# schematic.net
KiCad netlist of a schematic drawn in EAGLE
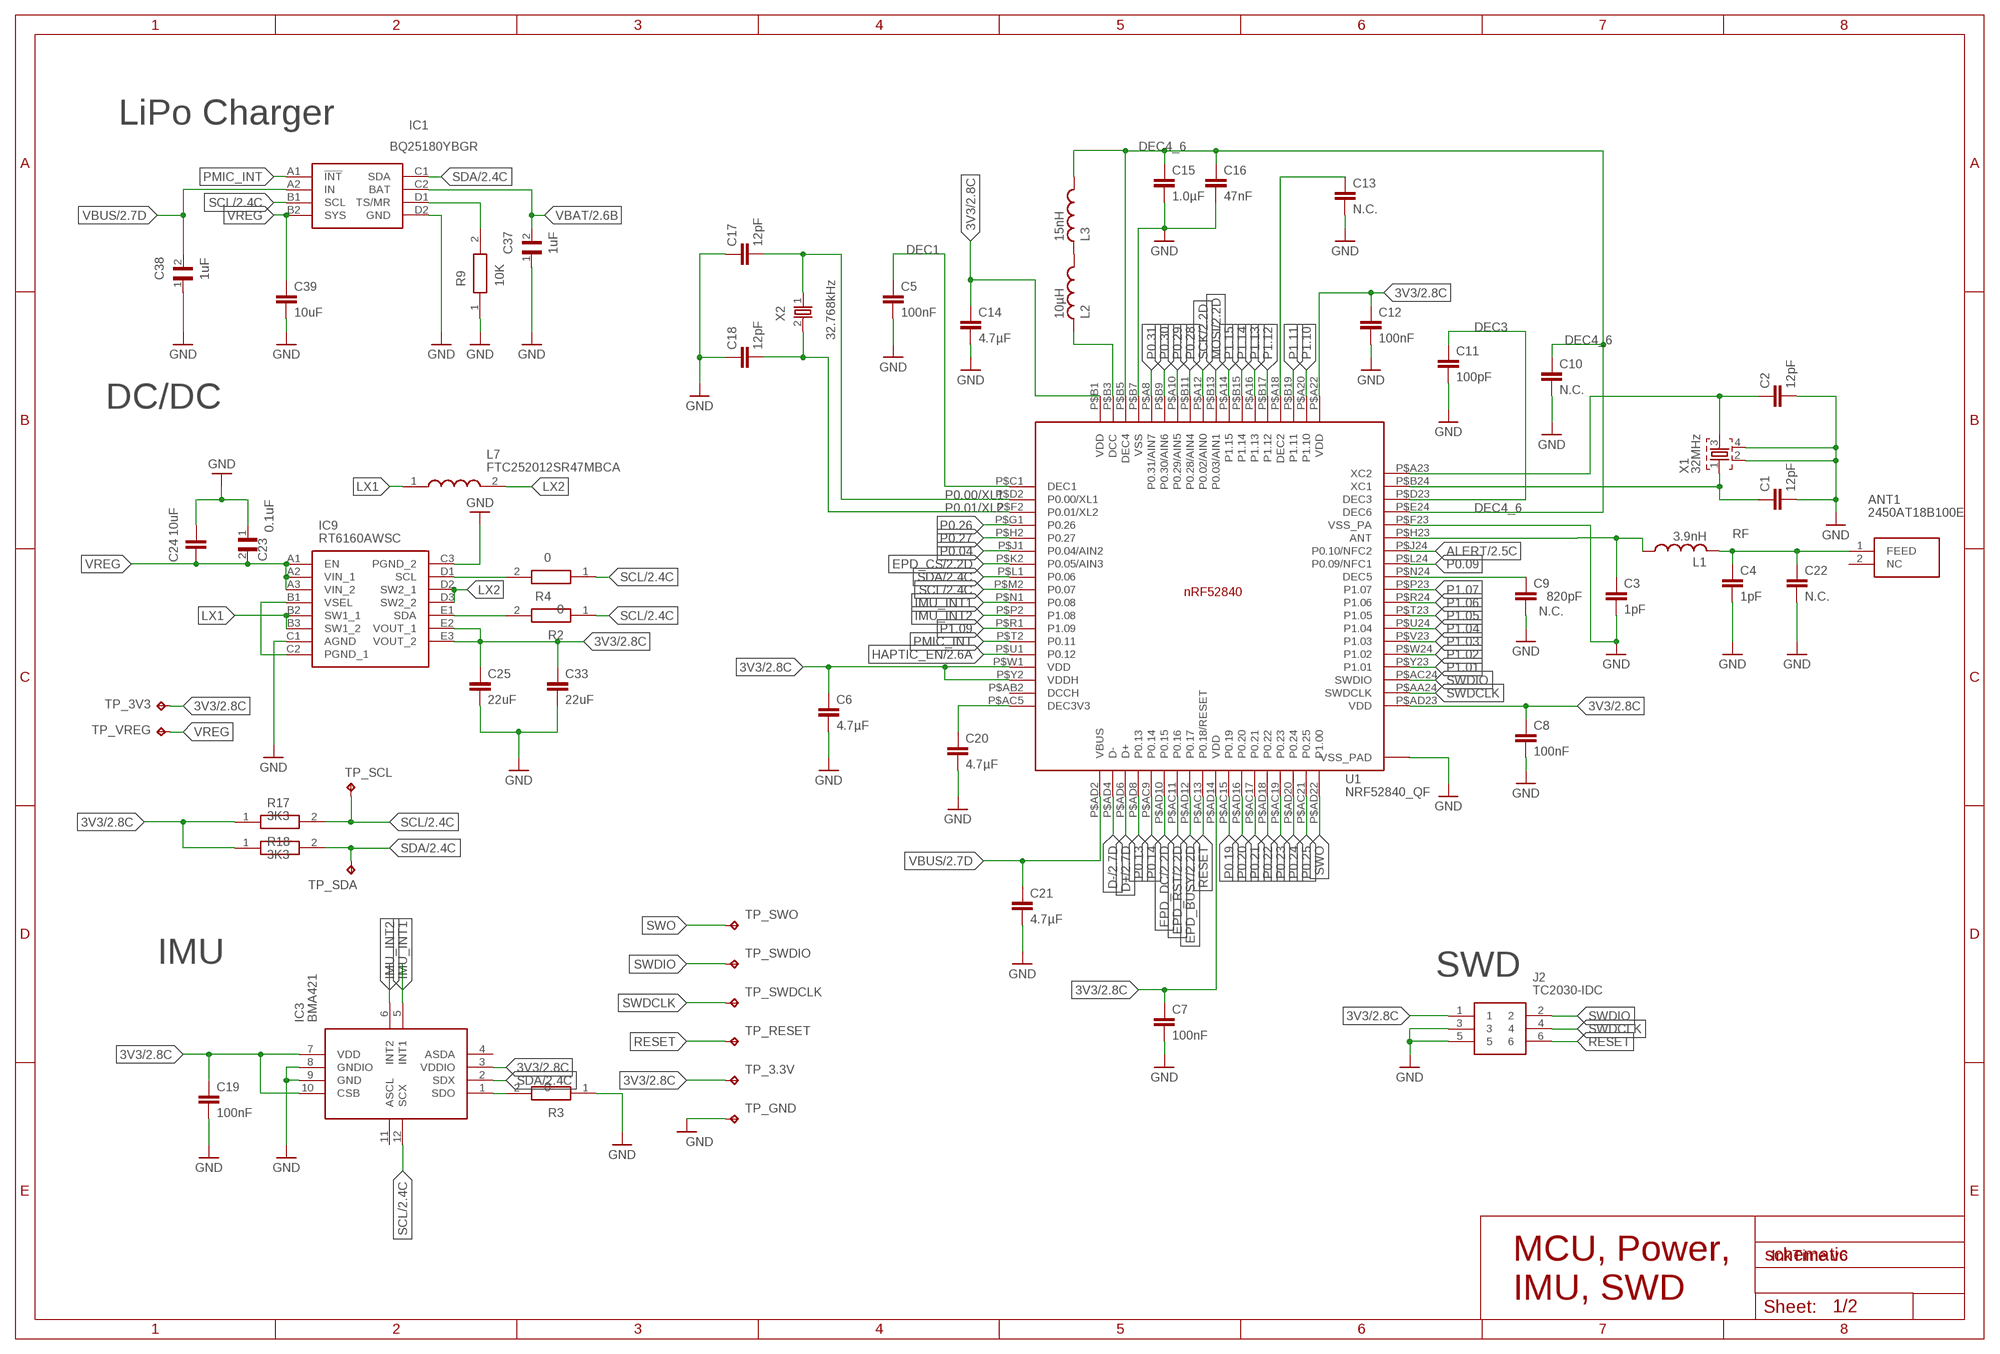
[diagram p0: schematic, sheet 1]
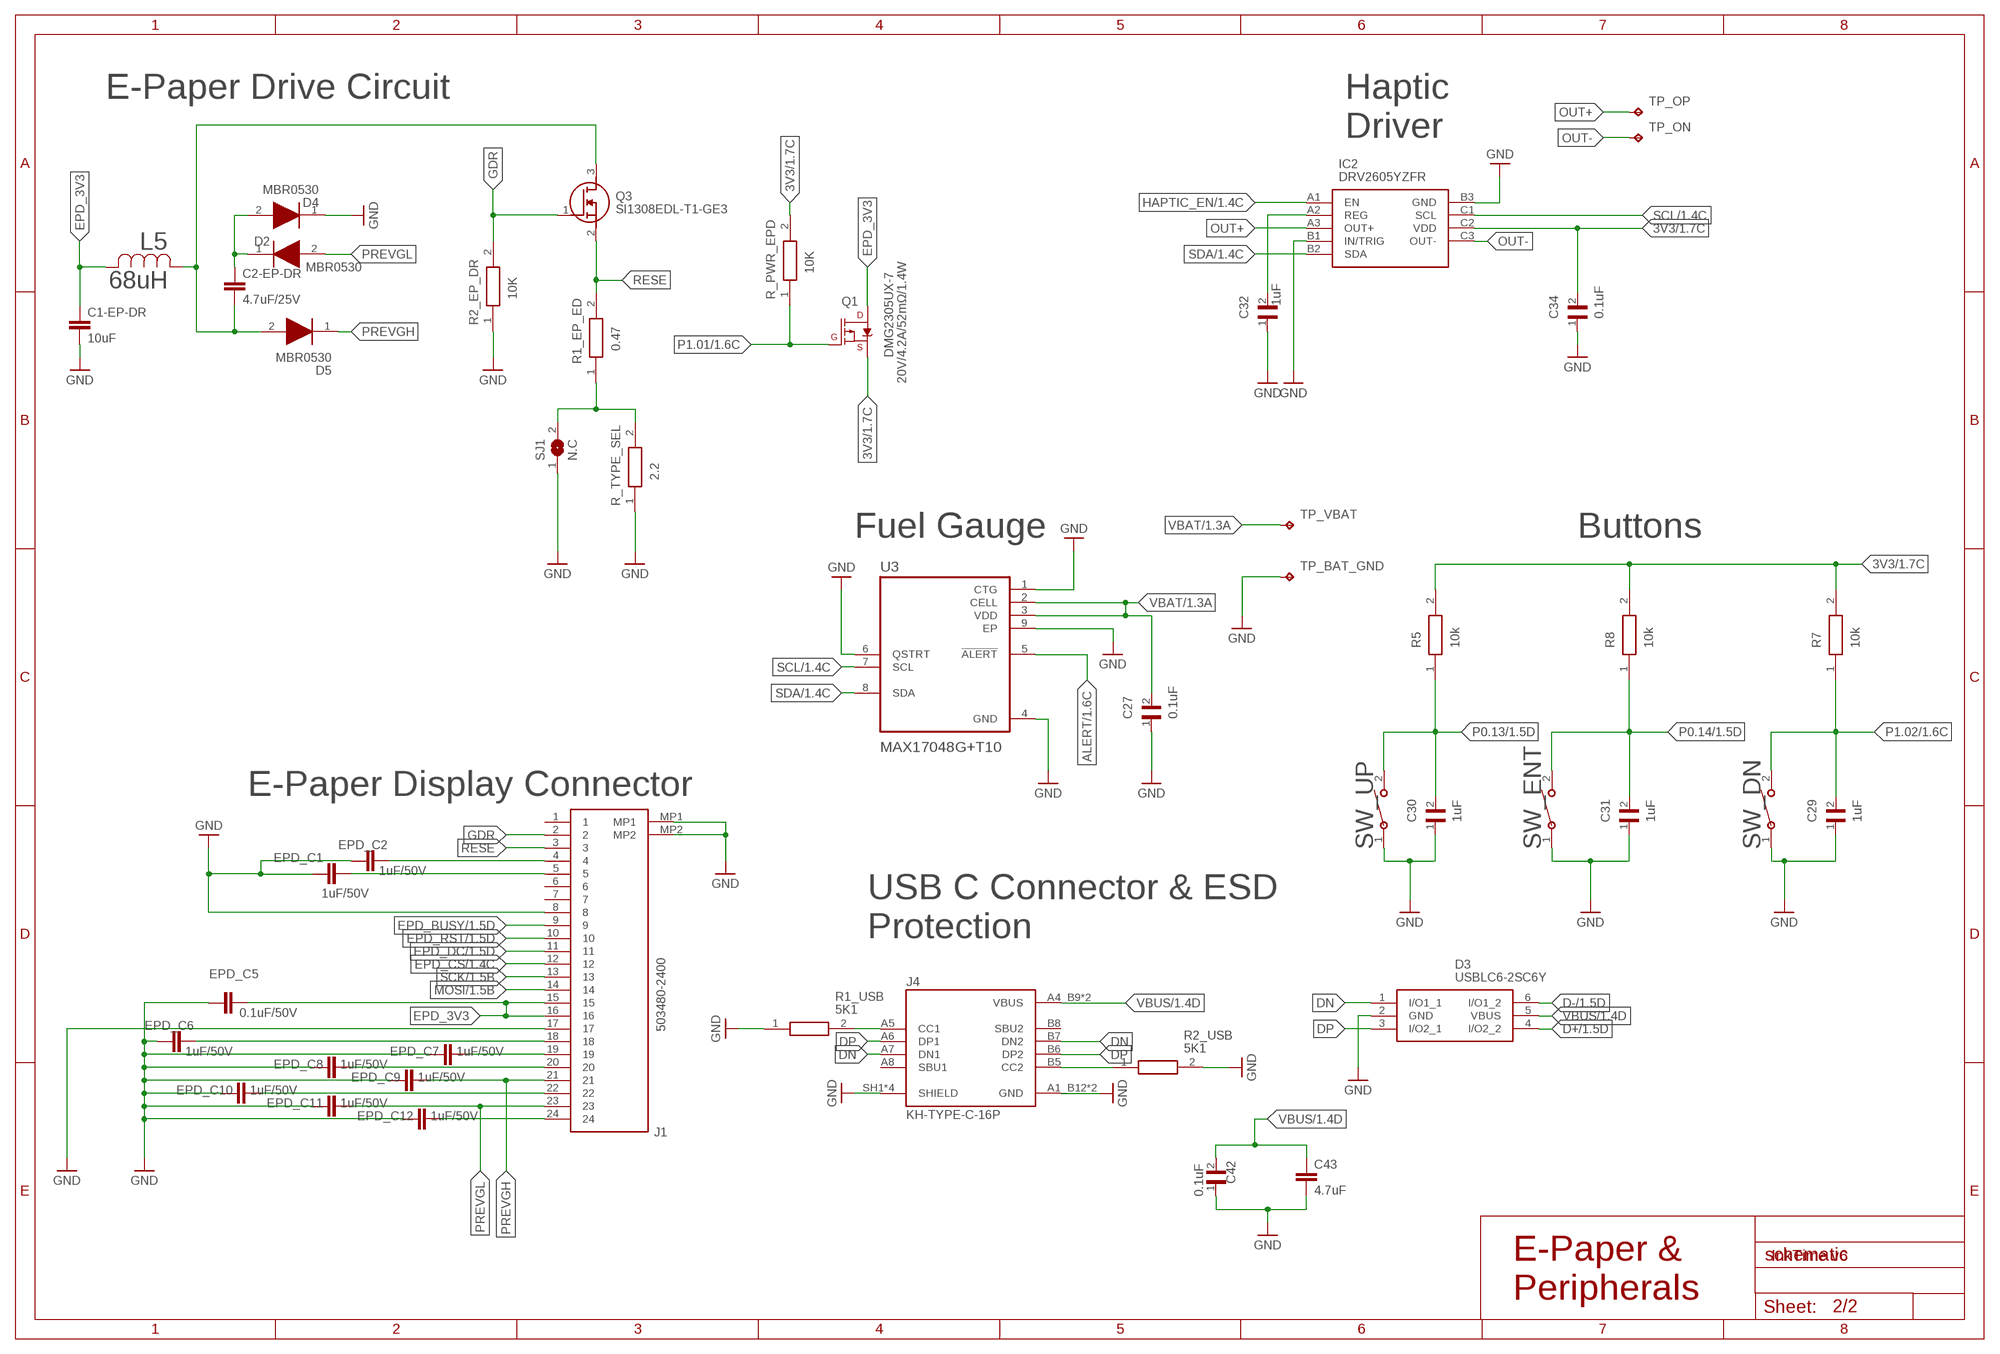
[diagram p1: schematic, sheet 2]

(export (version "E")
  (design (tool "Eeschema 10.0.6"))
  (components
    (comp (ref "C1-EP-DR")
      (value "10uF")
      (footprint "eagle-import:NORDIC_NRF_3_RESC0402_L")
      (libsource (lib "eagle-import") (part "NORDIC_NRF_3_CAPACITOR_0402_L"))
    )
    (comp (ref "C2-EP-DR")
      (value "4.7uF/25V")
      (footprint "eagle-import:NORDIC_NRF_3_RESC0402_L")
      (libsource (lib "eagle-import") (part "NORDIC_NRF_3_CAPACITOR_0402_L"))
    )
    (comp (ref "C27")
      (value "0.1uF")
      (footprint "eagle-import:GRM011R60J152KE01L_2_CAPC0201X13N")
      (fields (field (name "MF") "Murata") (field (name "MP") "GRM011R60J152KE01L"))
      (libsource (lib "eagle-import") (part "GRM011R60J152KE01L_2_GRM011R60J152KE01L"))
    )
    (comp (ref "C29")
      (value "1uF")
      (footprint "eagle-import:GRM011R60J152KE01L_2_CAPC0201X13N")
      (fields (field (name "MF") "Murata") (field (name "MP") "GRM011R60J152KE01L"))
      (libsource (lib "eagle-import") (part "GRM011R60J152KE01L_2_GRM011R60J152KE01L"))
    )
    (comp (ref "C30")
      (value "1uF")
      (footprint "eagle-import:GRM011R60J152KE01L_2_CAPC0201X13N")
      (fields (field (name "MF") "Murata") (field (name "MP") "GRM011R60J152KE01L"))
      (libsource (lib "eagle-import") (part "GRM011R60J152KE01L_2_GRM011R60J152KE01L"))
    )
    (comp (ref "C31")
      (value "1uF")
      (footprint "eagle-import:GRM011R60J152KE01L_2_CAPC0201X13N")
      (fields (field (name "MF") "Murata") (field (name "MP") "GRM011R60J152KE01L"))
      (libsource (lib "eagle-import") (part "GRM011R60J152KE01L_2_GRM011R60J152KE01L"))
    )
    (comp (ref "C32")
      (value "1uF")
      (footprint "eagle-import:GRM011R60J152KE01L_2_CAPC0201X13N")
      (fields (field (name "MF") "Murata") (field (name "MP") "GRM011R60J152KE01L"))
      (libsource (lib "eagle-import") (part "GRM011R60J152KE01L_2_GRM011R60J152KE01L"))
    )
    (comp (ref "C34")
      (value "0.1uF")
      (footprint "eagle-import:GRM011R60J152KE01L_2_CAPC0201X13N")
      (fields (field (name "MF") "Murata") (field (name "MP") "GRM011R60J152KE01L"))
      (libsource (lib "eagle-import") (part "GRM011R60J152KE01L_2_GRM011R60J152KE01L"))
    )
    (comp (ref "C42")
      (value "0.1uF")
      (footprint "eagle-import:GRM011R60J152KE01L_2_CAPC0201X13N")
      (fields (field (name "MF") "Murata") (field (name "MP") "GRM011R60J152KE01L"))
      (libsource (lib "eagle-import") (part "GRM011R60J152KE01L_2_GRM011R60J152KE01L"))
    )
    (comp (ref "C43")
      (value "4.7uF")
      (footprint "eagle-import:NORDIC_NRF_3_RESC0402_L")
      (libsource (lib "eagle-import") (part "NORDIC_NRF_3_CAPACITOR_0402_L"))
    )
    (comp (ref "D2")
      (value "MBR0530")
      (footprint "eagle-import:ESP32_C6_LIBRARY_5_SOD3716X135N")
      (fields (field (name "MF") "ON Semiconductor"))
      (libsource (lib "eagle-import") (part "ESP32_C6_LIBRARY_5_MBR0530"))
    )
    (comp (ref "D3")
      (value "USBLC6-2SC6Y")
      (footprint "eagle-import:ESP32_C6_LIBRARY_3_SOT95P280X145-6N")
      (fields (field (name "MF") "STMicroelectronics"))
      (libsource (lib "eagle-import") (part "ESP32_C6_LIBRARY_3_USBLC6-2SC6Y"))
    )
    (comp (ref "D4")
      (value "MBR0530")
      (footprint "eagle-import:ESP32_C6_LIBRARY_5_SOD3716X135N")
      (fields (field (name "MF") "ON Semiconductor"))
      (libsource (lib "eagle-import") (part "ESP32_C6_LIBRARY_5_MBR0530"))
    )
    (comp (ref "D5")
      (value "MBR0530")
      (footprint "eagle-import:ESP32_C6_LIBRARY_5_SOD3716X135N")
      (fields (field (name "MF") "ON Semiconductor"))
      (libsource (lib "eagle-import") (part "ESP32_C6_LIBRARY_5_MBR0530"))
    )
    (comp (ref "EPD_C1")
      (value "1uF/50V")
      (footprint "eagle-import:NORDIC_NRF_3_RESC0201_L")
      (libsource (lib "eagle-import") (part "NORDIC_NRF_3_CAPACITOR_0201_L"))
    )
    (comp (ref "EPD_C2")
      (value "1uF/50V")
      (footprint "eagle-import:NORDIC_NRF_3_RESC0201_L")
      (libsource (lib "eagle-import") (part "NORDIC_NRF_3_CAPACITOR_0201_L"))
    )
    (comp (ref "EPD_C5")
      (value "0.1uF/50V")
      (footprint "eagle-import:NORDIC_NRF_3_RESC0201_L")
      (libsource (lib "eagle-import") (part "NORDIC_NRF_3_CAPACITOR_0201_L"))
    )
    (comp (ref "EPD_C6")
      (value "1uF/50V")
      (footprint "eagle-import:NORDIC_NRF_3_RESC0402_L")
      (libsource (lib "eagle-import") (part "NORDIC_NRF_3_CAPACITOR_0402_L"))
    )
    (comp (ref "EPD_C7")
      (value "1uF/50V")
      (footprint "eagle-import:NORDIC_NRF_3_RESC0402_L")
      (libsource (lib "eagle-import") (part "NORDIC_NRF_3_CAPACITOR_0402_L"))
    )
    (comp (ref "EPD_C8")
      (value "1uF/50V")
      (footprint "eagle-import:NORDIC_NRF_3_RESC0402_L")
      (libsource (lib "eagle-import") (part "NORDIC_NRF_3_CAPACITOR_0402_L"))
    )
    (comp (ref "EPD_C9")
      (value "1uF/50V")
      (footprint "eagle-import:NORDIC_NRF_3_RESC0402_L")
      (libsource (lib "eagle-import") (part "NORDIC_NRF_3_CAPACITOR_0402_L"))
    )
    (comp (ref "EPD_C10")
      (value "1uF/50V")
      (footprint "eagle-import:NORDIC_NRF_3_RESC0402_L")
      (libsource (lib "eagle-import") (part "NORDIC_NRF_3_CAPACITOR_0402_L"))
    )
    (comp (ref "EPD_C11")
      (value "1uF/50V")
      (footprint "eagle-import:NORDIC_NRF_3_RESC0402_L")
      (libsource (lib "eagle-import") (part "NORDIC_NRF_3_CAPACITOR_0402_L"))
    )
    (comp (ref "EPD_C12")
      (value "1uF/50V")
      (footprint "eagle-import:NORDIC_NRF_3_RESC0402_L")
      (libsource (lib "eagle-import") (part "NORDIC_NRF_3_CAPACITOR_0402_L"))
    )
    (comp (ref "IC2")
      (value "DRV2605YZFR")
      (footprint "eagle-import:DRV2605YZFR_BGA9C50P3X3_144X144X62")
      (libsource (lib "eagle-import") (part "DRV2605YZFR_DRV2605YZFR"))
    )
    (comp (ref "J1")
      (value "503480-2400")
      (footprint "eagle-import:503480-2400_5034802400")
      (fields (field (name "MOUSER_PART_NUMBER") "538-503480-2400"))
      (libsource (lib "eagle-import") (part "503480-2400_503480-2400"))
    )
    (comp (ref "J4")
      (value "KH-TYPE-C-16P")
      (footprint "eagle-import:KH-TYPE-C-16P_KINGHELM_KH-TYPE-C-16P")
      (fields (field (name "MF") "kinghelm"))
      (libsource (lib "eagle-import") (part "KH-TYPE-C-16P_KH-TYPE-C-16P"))
    )
    (comp (ref "L5")
      (value "68uH")
      (footprint "eagle-import:ESP32_C6_LIBRARY_2_IND_4828-WE-TPC_WRE")
      (fields
        (field (name "MANUFACTURER_PART_NUMBER") "744043680")
        (field (name "COPYRIGHT") "Copyright (C) 2024 Ultra Librarian. All rights reserved.")
      )
      (libsource (lib "eagle-import") (part "ESP32_C6_LIBRARY_2_744043680IND_4828-WE-TPC_WRE"))
    )
    (comp (ref "Q1")
      (value "20V/4.2A/52mΩ/1.4W")
      (footprint "eagle-import:ESP32_C6_LIBRARY_4_ESP32_C6_LIBRARY_4_ESP32_C6_LIBRARY_4_ESP32_C6_LIBRARY_4_ESP32_WROVER_SPARKFUN-DISCRETESEMI_SOT23-3")
      (libsource (lib "eagle-import") (part "ESP32_C6_LIBRARY_4_ESP32_WROVER_SPARKFUN-DISCRETESEMI_MOSFET_PCH-DMG2305UX-7"))
    )
    (comp (ref "Q3")
      (value "SI1308EDL-T1-GE3")
      (footprint "eagle-import:ESP32_C6_LIBRARY_6_SOT65P210X110-3N")
      (fields (field (name "MF") "Vishay Siliconix"))
      (libsource (lib "eagle-import") (part "ESP32_C6_LIBRARY_6_SI1308EDL-T1-GE3"))
    )
    (comp (ref "R1_EP_ED")
      (value "0.47")
      (footprint "eagle-import:CPF0201D7K68C1_0201")
      (libsource (lib "eagle-import") (part "CPF0201D7K68C1_CPF0201D7K68C1"))
    )
    (comp (ref "R1_USB")
      (value "5K1")
      (footprint "eagle-import:CPF0201D7K68C1_0201")
      (libsource (lib "eagle-import") (part "CPF0201D7K68C1_CPF0201D7K68C1"))
    )
    (comp (ref "R2_EP_DR")
      (value "10K")
      (footprint "eagle-import:CPF0201D7K68C1_0201")
      (libsource (lib "eagle-import") (part "CPF0201D7K68C1_CPF0201D7K68C1"))
    )
    (comp (ref "R2_USB")
      (value "5K1")
      (footprint "eagle-import:CPF0201D7K68C1_0201")
      (libsource (lib "eagle-import") (part "CPF0201D7K68C1_CPF0201D7K68C1"))
    )
    (comp (ref "R5")
      (value "10k")
      (footprint "eagle-import:ERA-1AEB3401C_0201")
      (libsource (lib "eagle-import") (part "ERA-1AEB3401C_CPF0201D7K68C1"))
    )
    (comp (ref "R7")
      (value "10k")
      (footprint "eagle-import:ERA-1AEB3401C_0201")
      (libsource (lib "eagle-import") (part "ERA-1AEB3401C_CPF0201D7K68C1"))
    )
    (comp (ref "R8")
      (value "10k")
      (footprint "eagle-import:ERA-1AEB3401C_0201")
      (libsource (lib "eagle-import") (part "ERA-1AEB3401C_CPF0201D7K68C1"))
    )
    (comp (ref "R_PWR_EPD")
      (value "10K")
      (footprint "eagle-import:CPF0201D7K68C1_0201")
      (libsource (lib "eagle-import") (part "CPF0201D7K68C1_CPF0201D7K68C1"))
    )
    (comp (ref "R_TYPE_SEL")
      (value "2.2")
      (footprint "eagle-import:CPF0201D7K68C1_0201")
      (libsource (lib "eagle-import") (part "CPF0201D7K68C1_CPF0201D7K68C1"))
    )
    (comp (ref "SJ1")
      (value "N.C")
      (footprint "eagle-import:ESP32_C6_LIBRARY_7_JUMPER_SJ")
      (libsource (lib "eagle-import") (part "ESP32_C6_LIBRARY_7_JUMPER_SJ"))
    )
    (comp (ref "SW_DN")
      (value "2025-10-22_07-23-44_LIBRARY_EVP-AKE31ASW_EVP-AKE31A_PAN")
      (footprint "eagle-import:2025-10-22_07-23-44_LIBRARY_SW_EVP-AKE31A_PAN")
      (fields
        (field (name "MANUFACTURER_PART_NUMBER") "EVP-AKE31A")
        (field (name "COPYRIGHT") "Copyright (C) 2025 Ultra Librarian. All rights reserved.")
      )
      (libsource (lib "eagle-import") (part "2025-10-22_07-23-44_LIBRARY_EVP-AKE31ASW_EVP-AKE31A_PAN"))
    )
    (comp (ref "SW_ENT")
      (value "2025-10-22_07-23-44_LIBRARY_EVP-AKE31ASW_EVP-AKE31A_PAN")
      (footprint "eagle-import:2025-10-22_07-23-44_LIBRARY_SW_EVP-AKE31A_PAN")
      (fields
        (field (name "MANUFACTURER_PART_NUMBER") "EVP-AKE31A")
        (field (name "COPYRIGHT") "Copyright (C) 2025 Ultra Librarian. All rights reserved.")
      )
      (libsource (lib "eagle-import") (part "2025-10-22_07-23-44_LIBRARY_EVP-AKE31ASW_EVP-AKE31A_PAN"))
    )
    (comp (ref "SW_UP")
      (value "2025-10-22_07-23-44_LIBRARY_EVP-AKE31ASW_EVP-AKE31A_PAN")
      (footprint "eagle-import:2025-10-22_07-23-44_LIBRARY_SW_EVP-AKE31A_PAN")
      (fields
        (field (name "MANUFACTURER_PART_NUMBER") "EVP-AKE31A")
        (field (name "COPYRIGHT") "Copyright (C) 2025 Ultra Librarian. All rights reserved.")
      )
      (libsource (lib "eagle-import") (part "2025-10-22_07-23-44_LIBRARY_EVP-AKE31ASW_EVP-AKE31A_PAN"))
    )
    (comp (ref "TP_BAT_GND")
      (value "HECTOR_WATCH_1_TPTP20R")
      (footprint "eagle-import:HECTOR_WATCH_1_TP20R")
      (libsource (lib "eagle-import") (part "HECTOR_WATCH_1_TPTP20R"))
    )
    (comp (ref "TP_ON")
      (value "HECTOR_WATCH_1_TPTP20R")
      (footprint "eagle-import:HECTOR_WATCH_1_TP20R")
      (libsource (lib "eagle-import") (part "HECTOR_WATCH_1_TPTP20R"))
    )
    (comp (ref "TP_OP")
      (value "HECTOR_WATCH_1_TPTP20R")
      (footprint "eagle-import:HECTOR_WATCH_1_TP20R")
      (libsource (lib "eagle-import") (part "HECTOR_WATCH_1_TPTP20R"))
    )
    (comp (ref "TP_VBAT")
      (value "HECTOR_WATCH_1_TPTP20R")
      (footprint "eagle-import:HECTOR_WATCH_1_TP20R")
      (libsource (lib "eagle-import") (part "HECTOR_WATCH_1_TPTP20R"))
    )
    (comp (ref "U3")
      (value "MAX17048G+T10")
      (footprint "eagle-import:ESP32_C6_LIBRARY_SON50P200X200X80-9N")
      (fields (field (name "MF") "Analog Devices"))
      (libsource (lib "eagle-import") (part "ESP32_C6_LIBRARY_MAX17048G+T10"))
    )
    (comp (ref "ANT1")
      (value "2450AT18B100E")
      (footprint "eagle-import:2450AT18B100E_ANTC3216X140N")
      (fields (field (name "MOUSER_PART_NUMBER") "609-2450AT18B100E"))
      (libsource (lib "eagle-import") (part "2450AT18B100E_2450AT18B100E"))
    )
    (comp (ref "C1")
      (value "12pF")
      (footprint "eagle-import:NORDIC_NRF_3_RESC0201_L")
      (libsource (lib "eagle-import") (part "NORDIC_NRF_3_CAPACITOR_0201_L"))
    )
    (comp (ref "C2")
      (value "12pF")
      (footprint "eagle-import:NORDIC_NRF_3_RESC0201_L")
      (libsource (lib "eagle-import") (part "NORDIC_NRF_3_CAPACITOR_0201_L"))
    )
    (comp (ref "C3")
      (value "1pF")
      (footprint "eagle-import:NORDIC_NRF_3_RESC0201_L")
      (libsource (lib "eagle-import") (part "NORDIC_NRF_3_CAPACITOR_0201_L"))
    )
    (comp (ref "C4")
      (value "1pF")
      (footprint "eagle-import:NORDIC_NRF_3_RESC0201_L")
      (libsource (lib "eagle-import") (part "NORDIC_NRF_3_CAPACITOR_0201_L"))
    )
    (comp (ref "C5")
      (value "100nF")
      (footprint "eagle-import:NORDIC_NRF_3_RESC0201_L")
      (libsource (lib "eagle-import") (part "NORDIC_NRF_3_CAPACITOR_0201_L"))
    )
    (comp (ref "C6")
      (value "4.7µF")
      (footprint "eagle-import:NORDIC_NRF_3_RESC0402_L")
      (libsource (lib "eagle-import") (part "NORDIC_NRF_3_CAPACITOR_0402_L"))
    )
    (comp (ref "C7")
      (value "100nF")
      (footprint "eagle-import:NORDIC_NRF_3_RESC0201_L")
      (libsource (lib "eagle-import") (part "NORDIC_NRF_3_CAPACITOR_0201_L"))
    )
    (comp (ref "C8")
      (value "100nF")
      (footprint "eagle-import:NORDIC_NRF_3_RESC0201_L")
      (libsource (lib "eagle-import") (part "NORDIC_NRF_3_CAPACITOR_0201_L"))
    )
    (comp (ref "C9")
      (value "820pF")
      (footprint "eagle-import:NORDIC_NRF_3_RESC0201_L")
      (libsource (lib "eagle-import") (part "NORDIC_NRF_3_CAPACITOR_0201_L"))
    )
    (comp (ref "C10")
      (value "N.C.")
      (footprint "eagle-import:NORDIC_NRF_3_RESC0201_L")
      (libsource (lib "eagle-import") (part "NORDIC_NRF_3_CAPACITOR_0201_L"))
    )
    (comp (ref "C11")
      (value "100pF")
      (footprint "eagle-import:NORDIC_NRF_3_RESC0201_L")
      (libsource (lib "eagle-import") (part "NORDIC_NRF_3_CAPACITOR_0201_L"))
    )
    (comp (ref "C12")
      (value "100nF")
      (footprint "eagle-import:NORDIC_NRF_3_RESC0201_L")
      (libsource (lib "eagle-import") (part "NORDIC_NRF_3_CAPACITOR_0201_L"))
    )
    (comp (ref "C13")
      (value "N.C.")
      (footprint "eagle-import:NORDIC_NRF_3_RESC0201_L")
      (libsource (lib "eagle-import") (part "NORDIC_NRF_3_CAPACITOR_0201_L"))
    )
    (comp (ref "C14")
      (value "4.7µF")
      (footprint "eagle-import:NORDIC_NRF_3_RESC0402_L")
      (libsource (lib "eagle-import") (part "NORDIC_NRF_3_CAPACITOR_0402_L"))
    )
    (comp (ref "C15")
      (value "1.0µF")
      (footprint "eagle-import:NORDIC_NRF_3_RESC0402_L")
      (libsource (lib "eagle-import") (part "NORDIC_NRF_3_CAPACITOR_0402_L"))
    )
    (comp (ref "C16")
      (value "47nF")
      (footprint "eagle-import:NORDIC_NRF_3_RESC0201_L")
      (libsource (lib "eagle-import") (part "NORDIC_NRF_3_CAPACITOR_0201_L"))
    )
    (comp (ref "C17")
      (value "12pF")
      (footprint "eagle-import:NORDIC_NRF_3_RESC0201_L")
      (libsource (lib "eagle-import") (part "NORDIC_NRF_3_CAPACITOR_0201_L"))
    )
    (comp (ref "C18")
      (value "12pF")
      (footprint "eagle-import:NORDIC_NRF_3_RESC0201_L")
      (libsource (lib "eagle-import") (part "NORDIC_NRF_3_CAPACITOR_0201_L"))
    )
    (comp (ref "C19")
      (value "100nF")
      (footprint "eagle-import:NORDIC_NRF_3_RESC0201_L")
      (libsource (lib "eagle-import") (part "NORDIC_NRF_3_CAPACITOR_0201_L"))
    )
    (comp (ref "C20")
      (value "4.7µF")
      (footprint "eagle-import:NORDIC_NRF_3_RESC0402_L")
      (libsource (lib "eagle-import") (part "NORDIC_NRF_3_CAPACITOR_0402_L"))
    )
    (comp (ref "C21")
      (value "4.7µF")
      (footprint "eagle-import:NORDIC_NRF_3_RESC0402_L")
      (libsource (lib "eagle-import") (part "NORDIC_NRF_3_CAPACITOR_0402_L"))
    )
    (comp (ref "C22")
      (value "N.C.")
      (footprint "eagle-import:NORDIC_NRF_3_RESC0201_L")
      (libsource (lib "eagle-import") (part "NORDIC_NRF_3_CAPACITOR_0201_L"))
    )
    (comp (ref "C23")
      (value "0.1uF")
      (footprint "eagle-import:GRM011R60J152KE01L_2_CAPC0201X13N")
      (fields (field (name "MF") "Murata") (field (name "MP") "GRM011R60J152KE01L"))
      (libsource (lib "eagle-import") (part "GRM011R60J152KE01L_2_GRM011R60J152KE01L"))
    )
    (comp (ref "C24")
      (value "10uF")
      (footprint "eagle-import:NORDIC_NRF_3_RESC0201_L")
      (libsource (lib "eagle-import") (part "NORDIC_NRF_3_CAPACITOR_0201_L"))
    )
    (comp (ref "C25")
      (value "22uF")
      (footprint "eagle-import:NORDIC_NRF_3_RESC0201_L")
      (libsource (lib "eagle-import") (part "NORDIC_NRF_3_CAPACITOR_0201_L"))
    )
    (comp (ref "C33")
      (value "22uF")
      (footprint "eagle-import:NORDIC_NRF_3_RESC0201_L")
      (libsource (lib "eagle-import") (part "NORDIC_NRF_3_CAPACITOR_0201_L"))
    )
    (comp (ref "C37")
      (value "1uF")
      (footprint "eagle-import:GRM011R60J152KE01L_2_CAPC0201X13N")
      (fields (field (name "MF") "Murata") (field (name "MP") "GRM011R60J152KE01L"))
      (libsource (lib "eagle-import") (part "GRM011R60J152KE01L_2_GRM011R60J152KE01L"))
    )
    (comp (ref "C38")
      (value "1uF")
      (footprint "eagle-import:GRM011R60J152KE01L_2_CAPC0201X13N")
      (fields (field (name "MF") "Murata") (field (name "MP") "GRM011R60J152KE01L"))
      (libsource (lib "eagle-import") (part "GRM011R60J152KE01L_2_GRM011R60J152KE01L"))
    )
    (comp (ref "C39")
      (value "10uF")
      (footprint "eagle-import:PERFECT_0402_0402")
      (libsource (lib "eagle-import") (part "PERFECT_0402_CAP_0402"))
    )
    (comp (ref "IC1")
      (value "BQ25180YBGR_BQ25180YBGR")
      (footprint "eagle-import:BQ25180YBGR_BGA8C40P2X4_100X155X50")
      (fields
        (field (name "ARROW_PART_NUMBER") "BQ25180YBGR")
        (field (name "MANUFACTURER_PART_NUMBER") "BQ25180YBGR")
        (field (name "MOUSER_PART_NUMBER") "595-BQ25180YBGR")
      )
      (libsource (lib "eagle-import") (part "BQ25180YBGR_BQ25180YBGR"))
    )
    (comp (ref "IC3")
      (value "BMA421")
      (footprint "eagle-import:BMA423_BMA423")
      (fields (field (name "ARROW_PART_NUMBER") "BMA423") (field (name "MOUSER_PART_NUMBER") "262-BMA423"))
      (libsource (lib "eagle-import") (part "BMA423_BMA423"))
    )
    (comp (ref "IC9")
      (value "RT6160AWSC")
      (footprint "eagle-import:RT6160AWSC_BGA15C40P3X5_140X230X60")
      (fields (field (name "MOUSER_PART_NUMBER") "835-RT6160AWSC"))
      (libsource (lib "eagle-import") (part "RT6160AWSC_RT6160AWSC"))
    )
    (comp (ref "J2")
      (value "TC2030-IDC")
      (footprint "eagle-import:TC2030-IDC_TC2030IDC")
      (libsource (lib "eagle-import") (part "TC2030-IDC_TC2030-IDC"))
    )
    (comp (ref "L1")
      (value "3.9nH")
      (footprint "eagle-import:NORDIC_NRF_2_RESC0402_L")
      (libsource (lib "eagle-import") (part "NORDIC_NRF_2_INDUCTOR_0402_L"))
    )
    (comp (ref "L2")
      (value "10µH")
      (footprint "eagle-import:NORDIC_NRF_2_RESC0402_L")
      (libsource (lib "eagle-import") (part "NORDIC_NRF_2_INDUCTOR_0402_L"))
    )
    (comp (ref "L3")
      (value "15nH")
      (footprint "eagle-import:NORDIC_NRF_2_RESC0402_L")
      (libsource (lib "eagle-import") (part "NORDIC_NRF_2_INDUCTOR_0402_L"))
    )
    (comp (ref "L7")
      (value "FTC252012SR47MBCA")
      (footprint "eagle-import:MLP2016SR47MT0S1_INDC2016X100N")
      (libsource (lib "eagle-import") (part "MLP2016SR47MT0S1_FTC252012SR47MBCA"))
    )
    (comp (ref "R2")
      (value "0")
      (footprint "eagle-import:CPF0201D7K68C1_0201")
      (libsource (lib "eagle-import") (part "CPF0201D7K68C1_CPF0201D7K68C1"))
    )
    (comp (ref "R3")
      (value "0")
      (footprint "eagle-import:ERA-1AEB3401C_0201")
      (libsource (lib "eagle-import") (part "ERA-1AEB3401C_CPF0201D7K68C1"))
    )
    (comp (ref "R4")
      (value "0")
      (footprint "eagle-import:CPF0201D7K68C1_0201")
      (libsource (lib "eagle-import") (part "CPF0201D7K68C1_CPF0201D7K68C1"))
    )
    (comp (ref "R9")
      (value "10K")
      (footprint "eagle-import:ERA-1AEB3401C_0201")
      (libsource (lib "eagle-import") (part "ERA-1AEB3401C_CPF0201D7K68C1"))
    )
    (comp (ref "R17")
      (value "3K3")
      (footprint "eagle-import:CPF0201D7K68C1_0201")
      (libsource (lib "eagle-import") (part "CPF0201D7K68C1_CPF0201D7K68C1"))
    )
    (comp (ref "R18")
      (value "3K3")
      (footprint "eagle-import:CPF0201D7K68C1_0201")
      (libsource (lib "eagle-import") (part "CPF0201D7K68C1_CPF0201D7K68C1"))
    )
    (comp (ref "TP_3.3V")
      (value "HECTOR_WATCH_1_TPTP20R")
      (footprint "eagle-import:HECTOR_WATCH_1_TP20R")
      (libsource (lib "eagle-import") (part "HECTOR_WATCH_1_TPTP20R"))
    )
    (comp (ref "TP_3V3")
      (value "HECTOR_WATCH_1_TPTP20R")
      (footprint "eagle-import:HECTOR_WATCH_1_TP20R")
      (libsource (lib "eagle-import") (part "HECTOR_WATCH_1_TPTP20R"))
    )
    (comp (ref "TP_GND")
      (value "HECTOR_WATCH_1_TPTP20R")
      (footprint "eagle-import:HECTOR_WATCH_1_TP20R")
      (libsource (lib "eagle-import") (part "HECTOR_WATCH_1_TPTP20R"))
    )
    (comp (ref "TP_RESET")
      (value "HECTOR_WATCH_1_TPTP20R")
      (footprint "eagle-import:HECTOR_WATCH_1_TP20R")
      (libsource (lib "eagle-import") (part "HECTOR_WATCH_1_TPTP20R"))
    )
    (comp (ref "TP_SCL")
      (value "HECTOR_WATCH_1_TPTP20R")
      (footprint "eagle-import:HECTOR_WATCH_1_TP20R")
      (libsource (lib "eagle-import") (part "HECTOR_WATCH_1_TPTP20R"))
    )
    (comp (ref "TP_SDA")
      (value "HECTOR_WATCH_1_TPTP20R")
      (footprint "eagle-import:HECTOR_WATCH_1_TP20R")
      (libsource (lib "eagle-import") (part "HECTOR_WATCH_1_TPTP20R"))
    )
    (comp (ref "TP_SWDCLK")
      (value "HECTOR_WATCH_1_TPTP20R")
      (footprint "eagle-import:HECTOR_WATCH_1_TP20R")
      (libsource (lib "eagle-import") (part "HECTOR_WATCH_1_TPTP20R"))
    )
    (comp (ref "TP_SWDIO")
      (value "HECTOR_WATCH_1_TPTP20R")
      (footprint "eagle-import:HECTOR_WATCH_1_TP20R")
      (libsource (lib "eagle-import") (part "HECTOR_WATCH_1_TPTP20R"))
    )
    (comp (ref "TP_SWO")
      (value "HECTOR_WATCH_1_TPTP20R")
      (footprint "eagle-import:HECTOR_WATCH_1_TP20R")
      (libsource (lib "eagle-import") (part "HECTOR_WATCH_1_TPTP20R"))
    )
    (comp (ref "TP_VREG")
      (value "HECTOR_WATCH_1_TPTP20R")
      (footprint "eagle-import:HECTOR_WATCH_1_TP20R")
      (libsource (lib "eagle-import") (part "HECTOR_WATCH_1_TPTP20R"))
    )
    (comp (ref "U1")
      (value "NRF52840_QF")
      (footprint "eagle-import:NORDIC_NRF_4_AQFN50P700X700X85_HS-74N")
      (libsource (lib "eagle-import") (part "NORDIC_NRF_4_NRF52840_QF"))
    )
    (comp (ref "X1")
      (value "32MHz")
      (footprint "eagle-import:NORDIC_NRF_BT-XTAL_2016_N")
      (libsource (lib "eagle-import") (part "NORDIC_NRF_XTAL_32MHZ"))
    )
    (comp (ref "X2")
      (value "32.768kHz")
      (footprint "eagle-import:NORDIC_NRF_1_XTAL_3215_N")
      (libsource (lib "eagle-import") (part "NORDIC_NRF_1_XTAL_32KHZ"))
    )
  )
  (nets
    (net (code "1") (name "3V3") (class "Default")
      (node (ref "C12") (pin "1") (pinfunction "1_1") (pintype "passive"))
      (node (ref "C14") (pin "1") (pinfunction "1_1") (pintype "passive"))
      (node (ref "C19") (pin "1") (pinfunction "1_1") (pintype "passive"))
      (node (ref "C25") (pin "1") (pinfunction "1_1") (pintype "passive"))
      (node (ref "C33") (pin "1") (pinfunction "1_1") (pintype "passive"))
      (node (ref "C34") (pin "2") (pinfunction "2_2") (pintype "passive"))
      (node (ref "C6") (pin "1") (pinfunction "1_1") (pintype "passive"))
      (node (ref "C7") (pin "1") (pinfunction "1_1") (pintype "passive"))
      (node (ref "C8") (pin "1") (pinfunction "1_1") (pintype "passive"))
      (node (ref "IC2") (pin "C2") (pinfunction "VDD_C2") (pintype "bidirectional"))
      (node (ref "IC3") (pin "10") (pinfunction "CSB_10") (pintype "bidirectional"))
      (node (ref "IC3") (pin "3") (pinfunction "VDDIO_3") (pintype "bidirectional"))
      (node (ref "IC3") (pin "7") (pinfunction "VDD_7") (pintype "bidirectional"))
      (node (ref "IC9") (pin "E2") (pinfunction "VOUT_1_E2") (pintype "bidirectional"))
      (node (ref "IC9") (pin "E3") (pinfunction "VOUT_2_E3") (pintype "bidirectional"))
      (node (ref "J2") (pin "1") (pinfunction "1_1") (pintype "bidirectional"))
      (node (ref "Q1") (pin "2") (pinfunction "S_2") (pintype "bidirectional"))
      (node (ref "R17") (pin "1") (pinfunction "1_1") (pintype "bidirectional"))
      (node (ref "R18") (pin "1") (pinfunction "1_1") (pintype "bidirectional"))
      (node (ref "R5") (pin "2") (pinfunction "2_2") (pintype "bidirectional"))
      (node (ref "R7") (pin "2") (pinfunction "2_2") (pintype "bidirectional"))
      (node (ref "R8") (pin "2") (pinfunction "2_2") (pintype "bidirectional"))
      (node (ref "R_PWR_EPD") (pin "2") (pinfunction "2_2") (pintype "bidirectional"))
      (node (ref "TP_3.3V") (pin "TP") (pinfunction "TP_TP") (pintype "input"))
      (node (ref "TP_3V3") (pin "TP") (pinfunction "TP_TP") (pintype "input"))
      (node (ref "U1") (pin "P$A22") (pinfunction "VDD_P$A22") (pintype "power_in"))
      (node (ref "U1") (pin "P$AD14") (pinfunction "VDD_P$AD14") (pintype "power_in"))
      (node (ref "U1") (pin "P$AD23") (pinfunction "VDD_P$AD23") (pintype "power_in"))
      (node (ref "U1") (pin "P$B1") (pinfunction "VDD_P$B1") (pintype "power_in"))
      (node (ref "U1") (pin "P$W1") (pinfunction "VDD_P$W1") (pintype "power_in"))
      (node (ref "U1") (pin "P$Y2") (pinfunction "VDDH_P$Y2") (pintype "power_in"))
    )
    (net (code "2") (name "ALERT") (class "Default")
      (node (ref "U1") (pin "P$J24") (pinfunction "P0.10/NFC2_P$J24") (pintype "bidirectional"))
      (node (ref "U3") (pin "5") (pinfunction "~{ALERT}_5") (pintype "output"))
    )
    (net (code "3") (name "D+") (class "Default")
      (node (ref "D3") (pin "4") (pinfunction "I/O2_2_4") (pintype "bidirectional"))
      (node (ref "U1") (pin "P$AD6") (pinfunction "D+_P$AD6") (pintype "bidirectional"))
    )
    (net (code "4") (name "D-") (class "Default")
      (node (ref "D3") (pin "6") (pinfunction "I/O1_2_6") (pintype "bidirectional"))
      (node (ref "U1") (pin "P$AD4") (pinfunction "D-_P$AD4") (pintype "bidirectional"))
    )
    (net (code "5") (name "DEC1") (class "Default")
      (node (ref "C5") (pin "1") (pinfunction "1_1") (pintype "passive"))
      (node (ref "U1") (pin "P$C1") (pinfunction "DEC1_P$C1") (pintype "power_in"))
    )
    (net (code "6") (name "DEC3") (class "Default")
      (node (ref "C11") (pin "1") (pinfunction "1_1") (pintype "passive"))
      (node (ref "U1") (pin "P$D23") (pinfunction "DEC3_P$D23") (pintype "bidirectional"))
    )
    (net (code "7") (name "DEC4_6") (class "Default")
      (node (ref "C10") (pin "1") (pinfunction "1_1") (pintype "passive"))
      (node (ref "C15") (pin "1") (pinfunction "1_1") (pintype "passive"))
      (node (ref "C16") (pin "1") (pinfunction "1_1") (pintype "passive"))
      (node (ref "L3") (pin "1") (pinfunction "1_1") (pintype "passive"))
      (node (ref "U1") (pin "P$B5") (pinfunction "DEC4_P$B5") (pintype "power_in"))
      (node (ref "U1") (pin "P$E24") (pinfunction "DEC6_P$E24") (pintype "bidirectional"))
    )
    (net (code "8") (name "DN") (class "Default")
      (node (ref "D3") (pin "1") (pinfunction "I/O1_1_1") (pintype "bidirectional"))
      (node (ref "J4") (pin "A7") (pinfunction "DN1_A7") (pintype "bidirectional"))
      (node (ref "J4") (pin "B7") (pinfunction "DN2_B7") (pintype "bidirectional"))
    )
    (net (code "9") (name "DP") (class "Default")
      (node (ref "D3") (pin "3") (pinfunction "I/O2_1_3") (pintype "bidirectional"))
      (node (ref "J4") (pin "A6") (pinfunction "DP1_A6") (pintype "bidirectional"))
      (node (ref "J4") (pin "B6") (pinfunction "DP2_B6") (pintype "bidirectional"))
    )
    (net (code "10") (name "EPD_3V3") (class "Default")
      (node (ref "C1-EP-DR") (pin "1") (pinfunction "1_1") (pintype "passive"))
      (node (ref "EPD_C5") (pin "2") (pinfunction "2_2") (pintype "passive"))
      (node (ref "J1") (pin "15") (pinfunction "15_15") (pintype "bidirectional"))
      (node (ref "J1") (pin "16") (pinfunction "16_16") (pintype "bidirectional"))
      (node (ref "L5") (pin "2") (pinfunction "2_2") (pintype "passive"))
      (node (ref "Q1") (pin "3") (pinfunction "D_3") (pintype "bidirectional"))
    )
    (net (code "11") (name "EPD_BUSY") (class "Default")
      (node (ref "J1") (pin "9") (pinfunction "9_9") (pintype "bidirectional"))
      (node (ref "U1") (pin "P$AD12") (pinfunction "P0.17_P$AD12") (pintype "bidirectional"))
    )
    (net (code "12") (name "EPD_CS") (class "Default")
      (node (ref "J1") (pin "12") (pinfunction "12_12") (pintype "bidirectional"))
      (node (ref "U1") (pin "P$K2") (pinfunction "P0.05/AIN3_P$K2") (pintype "bidirectional"))
    )
    (net (code "13") (name "EPD_DC") (class "Default")
      (node (ref "J1") (pin "11") (pinfunction "11_11") (pintype "bidirectional"))
      (node (ref "U1") (pin "P$AD10") (pinfunction "P0.15_P$AD10") (pintype "bidirectional"))
    )
    (net (code "14") (name "EPD_RST") (class "Default")
      (node (ref "J1") (pin "10") (pinfunction "10_10") (pintype "bidirectional"))
      (node (ref "U1") (pin "P$AC11") (pinfunction "P0.16_P$AC11") (pintype "bidirectional"))
    )
    (net (code "15") (name "GDR") (class "Default")
      (node (ref "J1") (pin "2") (pinfunction "2_2") (pintype "bidirectional"))
      (node (ref "Q3") (pin "1") (pinfunction "G_1") (pintype "bidirectional"))
      (node (ref "R2_EP_DR") (pin "2") (pinfunction "2_2") (pintype "bidirectional"))
    )
    (net (code "16") (name "GND") (class "Default")
      (node (ref "C1") (pin "2") (pinfunction "2_2") (pintype "passive"))
      (node (ref "C1-EP-DR") (pin "2") (pinfunction "2_2") (pintype "passive"))
      (node (ref "C10") (pin "2") (pinfunction "2_2") (pintype "passive"))
      (node (ref "C11") (pin "2") (pinfunction "2_2") (pintype "passive"))
      (node (ref "C12") (pin "2") (pinfunction "2_2") (pintype "passive"))
      (node (ref "C13") (pin "2") (pinfunction "2_2") (pintype "passive"))
      (node (ref "C14") (pin "2") (pinfunction "2_2") (pintype "passive"))
      (node (ref "C15") (pin "2") (pinfunction "2_2") (pintype "passive"))
      (node (ref "C16") (pin "2") (pinfunction "2_2") (pintype "passive"))
      (node (ref "C17") (pin "1") (pinfunction "1_1") (pintype "passive"))
      (node (ref "C18") (pin "1") (pinfunction "1_1") (pintype "passive"))
      (node (ref "C19") (pin "2") (pinfunction "2_2") (pintype "passive"))
      (node (ref "C2") (pin "2") (pinfunction "2_2") (pintype "passive"))
      (node (ref "C20") (pin "2") (pinfunction "2_2") (pintype "passive"))
      (node (ref "C21") (pin "2") (pinfunction "2_2") (pintype "passive"))
      (node (ref "C22") (pin "2") (pinfunction "2_2") (pintype "passive"))
      (node (ref "C23") (pin "1") (pinfunction "1_1") (pintype "passive"))
      (node (ref "C24") (pin "1") (pinfunction "1_1") (pintype "passive"))
      (node (ref "C25") (pin "2") (pinfunction "2_2") (pintype "passive"))
      (node (ref "C27") (pin "1") (pinfunction "1_1") (pintype "passive"))
      (node (ref "C29") (pin "1") (pinfunction "1_1") (pintype "passive"))
      (node (ref "C3") (pin "2") (pinfunction "2_2") (pintype "passive"))
      (node (ref "C30") (pin "1") (pinfunction "1_1") (pintype "passive"))
      (node (ref "C31") (pin "1") (pinfunction "1_1") (pintype "passive"))
      (node (ref "C32") (pin "1") (pinfunction "1_1") (pintype "passive"))
      (node (ref "C33") (pin "2") (pinfunction "2_2") (pintype "passive"))
      (node (ref "C34") (pin "1") (pinfunction "1_1") (pintype "passive"))
      (node (ref "C37") (pin "1") (pinfunction "1_1") (pintype "passive"))
      (node (ref "C38") (pin "1") (pinfunction "1_1") (pintype "passive"))
      (node (ref "C39") (pin "2") (pinfunction "2_2") (pintype "passive"))
      (node (ref "C4") (pin "2") (pinfunction "2_2") (pintype "passive"))
      (node (ref "C42") (pin "1") (pinfunction "1_1") (pintype "passive"))
      (node (ref "C43") (pin "2") (pinfunction "2_2") (pintype "passive"))
      (node (ref "C5") (pin "2") (pinfunction "2_2") (pintype "passive"))
      (node (ref "C6") (pin "2") (pinfunction "2_2") (pintype "passive"))
      (node (ref "C7") (pin "2") (pinfunction "2_2") (pintype "passive"))
      (node (ref "C8") (pin "2") (pinfunction "2_2") (pintype "passive"))
      (node (ref "C9") (pin "2") (pinfunction "2_2") (pintype "passive"))
      (node (ref "D3") (pin "2") (pinfunction "GND_2") (pintype "bidirectional"))
      (node (ref "D4") (pin "1") (pinfunction "K_1") (pintype "bidirectional"))
      (node (ref "EPD_C1") (pin "1") (pinfunction "1_1") (pintype "passive"))
      (node (ref "EPD_C10") (pin "1") (pinfunction "1_1") (pintype "passive"))
      (node (ref "EPD_C11") (pin "1") (pinfunction "1_1") (pintype "passive"))
      (node (ref "EPD_C12") (pin "1") (pinfunction "1_1") (pintype "passive"))
      (node (ref "EPD_C2") (pin "1") (pinfunction "1_1") (pintype "passive"))
      (node (ref "EPD_C5") (pin "1") (pinfunction "1_1") (pintype "passive"))
      (node (ref "EPD_C6") (pin "1") (pinfunction "1_1") (pintype "passive"))
      (node (ref "EPD_C7") (pin "1") (pinfunction "1_1") (pintype "passive"))
      (node (ref "EPD_C8") (pin "1") (pinfunction "1_1") (pintype "passive"))
      (node (ref "EPD_C9") (pin "1") (pinfunction "1_1") (pintype "passive"))
      (node (ref "IC1") (pin "D2") (pinfunction "GND_D2") (pintype "bidirectional"))
      (node (ref "IC2") (pin "B1") (pinfunction "IN/TRIG_B1") (pintype "bidirectional"))
      (node (ref "IC2") (pin "B3") (pinfunction "GND_B3") (pintype "bidirectional"))
      (node (ref "IC3") (pin "8") (pinfunction "GNDIO_8") (pintype "bidirectional"))
      (node (ref "IC3") (pin "9") (pinfunction "GND_9") (pintype "bidirectional"))
      (node (ref "IC9") (pin "C1") (pinfunction "AGND_C1") (pintype "bidirectional"))
      (node (ref "IC9") (pin "C3") (pinfunction "PGND_2_C3") (pintype "bidirectional"))
      (node (ref "J1") (pin "17") (pinfunction "17_17") (pintype "bidirectional"))
      (node (ref "J1") (pin "8") (pinfunction "8_8") (pintype "bidirectional"))
      (node (ref "J1") (pin "MP1") (pinfunction "MP1_MP1") (pintype "bidirectional"))
      (node (ref "J1") (pin "MP2") (pinfunction "MP2_MP2") (pintype "bidirectional"))
      (node (ref "J2") (pin "3") (pinfunction "3_3") (pintype "bidirectional"))
      (node (ref "J2") (pin "5") (pinfunction "5_5") (pintype "bidirectional"))
      (node (ref "J4") (pin "A12_B1") (pinfunction "GND_A12_B1") (pintype "power_in"))
      (node (ref "J4") (pin "A1_B12") (pinfunction "GND_A1_B12") (pintype "power_in"))
      (node (ref "J4") (pin "SH1") (pinfunction "SHIELD_SH1") (pintype "passive"))
      (node (ref "J4") (pin "SH2") (pinfunction "SHIELD_SH2") (pintype "passive"))
      (node (ref "J4") (pin "SH3") (pinfunction "SHIELD_SH3") (pintype "passive"))
      (node (ref "J4") (pin "SH4") (pinfunction "SHIELD_SH4") (pintype "passive"))
      (node (ref "R1_USB") (pin "1") (pinfunction "1_1") (pintype "bidirectional"))
      (node (ref "R2_EP_DR") (pin "1") (pinfunction "1_1") (pintype "bidirectional"))
      (node (ref "R2_USB") (pin "2") (pinfunction "2_2") (pintype "bidirectional"))
      (node (ref "R3") (pin "1") (pinfunction "1_1") (pintype "bidirectional"))
      (node (ref "R9") (pin "1") (pinfunction "1_1") (pintype "bidirectional"))
      (node (ref "R_TYPE_SEL") (pin "1") (pinfunction "1_1") (pintype "bidirectional"))
      (node (ref "SJ1") (pin "1") (pinfunction "1_1") (pintype "passive"))
      (node (ref "SW_DN") (pin "1") (pinfunction "1_1") (pintype "passive"))
      (node (ref "SW_ENT") (pin "1") (pinfunction "1_1") (pintype "passive"))
      (node (ref "SW_UP") (pin "1") (pinfunction "1_1") (pintype "passive"))
      (node (ref "TP_BAT_GND") (pin "TP") (pinfunction "TP_TP") (pintype "input"))
      (node (ref "TP_GND") (pin "TP") (pinfunction "TP_TP") (pintype "input"))
      (node (ref "U1") (pin "P$74") (pinfunction "VSS_PAD_P$74") (pintype "bidirectional"))
      (node (ref "U1") (pin "P$75") (pinfunction "VSS_PAD_P$75") (pintype "bidirectional"))
      (node (ref "U1") (pin "P$76") (pinfunction "VSS_PAD_P$76") (pintype "bidirectional"))
      (node (ref "U1") (pin "P$77") (pinfunction "VSS_PAD_P$77") (pintype "bidirectional"))
      (node (ref "U1") (pin "P$78") (pinfunction "VSS_PAD_P$78") (pintype "bidirectional"))
      (node (ref "U1") (pin "P$79") (pinfunction "VSS_PAD_P$79") (pintype "bidirectional"))
      (node (ref "U1") (pin "P$80") (pinfunction "VSS_PAD_P$80") (pintype "bidirectional"))
      (node (ref "U1") (pin "P$81") (pinfunction "VSS_PAD_P$81") (pintype "bidirectional"))
      (node (ref "U1") (pin "P$82") (pinfunction "VSS_PAD_P$82") (pintype "bidirectional"))
      (node (ref "U1") (pin "P$83") (pinfunction "VSS_PAD_P$83") (pintype "bidirectional"))
      (node (ref "U1") (pin "P$84") (pinfunction "VSS_PAD_P$84") (pintype "bidirectional"))
      (node (ref "U1") (pin "P$85") (pinfunction "VSS_PAD_P$85") (pintype "bidirectional"))
      (node (ref "U1") (pin "P$86") (pinfunction "VSS_PAD_P$86") (pintype "bidirectional"))
      (node (ref "U1") (pin "P$87") (pinfunction "VSS_PAD_P$87") (pintype "bidirectional"))
      (node (ref "U1") (pin "P$88") (pinfunction "VSS_PAD_P$88") (pintype "bidirectional"))
      (node (ref "U1") (pin "P$89") (pinfunction "VSS_PAD_P$89") (pintype "bidirectional"))
      (node (ref "U1") (pin "P$90") (pinfunction "VSS_PAD_P$90") (pintype "bidirectional"))
      (node (ref "U1") (pin "P$B7") (pinfunction "VSS_P$B7") (pintype "power_in"))
      (node (ref "U1") (pin "P$F23") (pinfunction "VSS_PA_P$F23") (pintype "bidirectional"))
      (node (ref "U3") (pin "1") (pinfunction "CTG_1") (pintype "power_in"))
      (node (ref "U3") (pin "4") (pinfunction "GND_4") (pintype "power_in"))
      (node (ref "U3") (pin "6") (pinfunction "QSTRT_6") (pintype "input"))
      (node (ref "U3") (pin "9") (pinfunction "EP_9") (pintype "power_in"))
      (node (ref "X1") (pin "2") (pinfunction "2_2") (pintype "passive"))
      (node (ref "X1") (pin "4") (pinfunction "4_4") (pintype "passive"))
    )
    (net (code "17") (name "HAPTIC_EN") (class "Default")
      (node (ref "IC2") (pin "A1") (pinfunction "EN_A1") (pintype "bidirectional"))
      (node (ref "U1") (pin "P$U1") (pinfunction "P0.12_P$U1") (pintype "bidirectional"))
    )
    (net (code "18") (name "IMU_INT1") (class "Default")
      (node (ref "IC3") (pin "5") (pinfunction "INT1_5") (pintype "bidirectional"))
      (node (ref "U1") (pin "P$N1") (pinfunction "P0.08_P$N1") (pintype "bidirectional"))
    )
    (net (code "19") (name "IMU_INT2") (class "Default")
      (node (ref "IC3") (pin "6") (pinfunction "INT2_6") (pintype "bidirectional"))
      (node (ref "U1") (pin "P$P2") (pinfunction "P1.08_P$P2") (pintype "bidirectional"))
    )
    (net (code "20") (name "LX1") (class "Default")
      (node (ref "IC9") (pin "B2") (pinfunction "SW1_1_B2") (pintype "bidirectional"))
      (node (ref "IC9") (pin "B3") (pinfunction "SW1_2_B3") (pintype "bidirectional"))
      (node (ref "L7") (pin "1") (pinfunction "1_1") (pintype "bidirectional"))
    )
    (net (code "21") (name "LX2") (class "Default")
      (node (ref "IC9") (pin "D2") (pinfunction "SW2_1_D2") (pintype "bidirectional"))
      (node (ref "IC9") (pin "D3") (pinfunction "SW2_2_D3") (pintype "bidirectional"))
      (node (ref "L7") (pin "2") (pinfunction "2_2") (pintype "bidirectional"))
    )
    (net (code "22") (name "MOSI") (class "Default")
      (node (ref "J1") (pin "14") (pinfunction "14_14") (pintype "bidirectional"))
      (node (ref "U1") (pin "P$B13") (pinfunction "P0.03/AIN1_P$B13") (pintype "bidirectional"))
    )
    (net (code "23") (name "Net-(D2-K)") (class "Default")
      (node (ref "C2-EP-DR") (pin "1") (pinfunction "1_1") (pintype "passive"))
      (node (ref "D2") (pin "1") (pinfunction "K_1") (pintype "bidirectional"))
      (node (ref "D4") (pin "2") (pinfunction "A_2") (pintype "bidirectional"))
    )
    (net (code "24") (name "Net-(D5-A)") (class "Default")
      (node (ref "C2-EP-DR") (pin "2") (pinfunction "2_2") (pintype "passive"))
      (node (ref "D5") (pin "2") (pinfunction "A_2") (pintype "bidirectional"))
      (node (ref "L5") (pin "1") (pinfunction "1_1") (pintype "passive"))
      (node (ref "Q3") (pin "3") (pinfunction "D_3") (pintype "bidirectional"))
    )
    (net (code "25") (name "Net-(EPD_C1-Pad2)") (class "Default")
      (node (ref "EPD_C1") (pin "2") (pinfunction "2_2") (pintype "passive"))
      (node (ref "J1") (pin "5") (pinfunction "5_5") (pintype "bidirectional"))
    )
    (net (code "26") (name "Net-(EPD_C2-Pad2)") (class "Default")
      (node (ref "EPD_C2") (pin "2") (pinfunction "2_2") (pintype "passive"))
      (node (ref "J1") (pin "4") (pinfunction "4_4") (pintype "bidirectional"))
    )
    (net (code "27") (name "Net-(EPD_C6-Pad2)") (class "Default")
      (node (ref "EPD_C6") (pin "2") (pinfunction "2_2") (pintype "passive"))
      (node (ref "J1") (pin "18") (pinfunction "18_18") (pintype "bidirectional"))
    )
    (net (code "28") (name "Net-(EPD_C7-Pad2)") (class "Default")
      (node (ref "EPD_C7") (pin "2") (pinfunction "2_2") (pintype "passive"))
      (node (ref "J1") (pin "19") (pinfunction "19_19") (pintype "bidirectional"))
    )
    (net (code "29") (name "Net-(EPD_C8-Pad2)") (class "Default")
      (node (ref "EPD_C8") (pin "2") (pinfunction "2_2") (pintype "passive"))
      (node (ref "J1") (pin "20") (pinfunction "20_20") (pintype "bidirectional"))
    )
    (net (code "30") (name "Net-(EPD_C10-Pad2)") (class "Default")
      (node (ref "EPD_C10") (pin "2") (pinfunction "2_2") (pintype "passive"))
      (node (ref "J1") (pin "22") (pinfunction "22_22") (pintype "bidirectional"))
    )
    (net (code "31") (name "Net-(EPD_C12-Pad2)") (class "Default")
      (node (ref "EPD_C12") (pin "2") (pinfunction "2_2") (pintype "passive"))
      (node (ref "J1") (pin "24") (pinfunction "24_24") (pintype "bidirectional"))
    )
    (net (code "32") (name "Net-(IC1-TS{slash}MR)") (class "Default")
      (node (ref "IC1") (pin "D1") (pinfunction "TS/MR_D1") (pintype "bidirectional"))
      (node (ref "R9") (pin "2") (pinfunction "2_2") (pintype "bidirectional"))
    )
    (net (code "33") (name "Net-(IC2-REG)") (class "Default")
      (node (ref "C32") (pin "2") (pinfunction "2_2") (pintype "passive"))
      (node (ref "IC2") (pin "A2") (pinfunction "REG_A2") (pintype "bidirectional"))
    )
    (net (code "34") (name "Net-(IC3-SDO)") (class "Default")
      (node (ref "IC3") (pin "1") (pinfunction "SDO_1") (pintype "bidirectional"))
      (node (ref "R3") (pin "2") (pinfunction "2_2") (pintype "bidirectional"))
    )
    (net (code "35") (name "Net-(IC9-PGND_1)") (class "Default")
      (node (ref "IC9") (pin "B1") (pinfunction "VSEL_B1") (pintype "bidirectional"))
      (node (ref "IC9") (pin "C2") (pinfunction "PGND_1_C2") (pintype "bidirectional"))
    )
    (net (code "36") (name "Net-(IC9-SCL)") (class "Default")
      (node (ref "IC9") (pin "D1") (pinfunction "SCL_D1") (pintype "bidirectional"))
      (node (ref "R4") (pin "2") (pinfunction "2_2") (pintype "bidirectional"))
    )
    (net (code "37") (name "Net-(IC9-SDA)") (class "Default")
      (node (ref "IC9") (pin "E1") (pinfunction "SDA_E1") (pintype "bidirectional"))
      (node (ref "R2") (pin "2") (pinfunction "2_2") (pintype "bidirectional"))
    )
    (net (code "38") (name "Net-(J4-CC1)") (class "Default")
      (node (ref "J4") (pin "A5") (pinfunction "CC1_A5") (pintype "bidirectional"))
      (node (ref "R1_USB") (pin "2") (pinfunction "2_2") (pintype "bidirectional"))
    )
    (net (code "39") (name "Net-(J4-CC2)") (class "Default")
      (node (ref "J4") (pin "B5") (pinfunction "CC2_B5") (pintype "bidirectional"))
      (node (ref "R2_USB") (pin "1") (pinfunction "1_1") (pintype "bidirectional"))
    )
    (net (code "40") (name "Net-(L2-Pad1)") (class "Default")
      (node (ref "L2") (pin "1") (pinfunction "1_1") (pintype "passive"))
      (node (ref "L3") (pin "2") (pinfunction "2_2") (pintype "passive"))
    )
    (net (code "41") (name "Net-(R1_EP_ED-Pad1)") (class "Default")
      (node (ref "R1_EP_ED") (pin "1") (pinfunction "1_1") (pintype "bidirectional"))
      (node (ref "R_TYPE_SEL") (pin "2") (pinfunction "2_2") (pintype "bidirectional"))
      (node (ref "SJ1") (pin "2") (pinfunction "2_2") (pintype "passive"))
    )
    (net (code "42") (name "Net-(U1-ANT)") (class "Default")
      (node (ref "C3") (pin "1") (pinfunction "1_1") (pintype "passive"))
      (node (ref "L1") (pin "1") (pinfunction "1_1") (pintype "passive"))
      (node (ref "U1") (pin "P$H23") (pinfunction "ANT_P$H23") (pintype "bidirectional"))
    )
    (net (code "43") (name "Net-(U1-DCC)") (class "Default")
      (node (ref "L2") (pin "2") (pinfunction "2_2") (pintype "passive"))
      (node (ref "U1") (pin "P$B3") (pinfunction "DCC_P$B3") (pintype "output"))
    )
    (net (code "44") (name "Net-(U1-DEC2)") (class "Default")
      (node (ref "C13") (pin "1") (pinfunction "1_1") (pintype "passive"))
      (node (ref "U1") (pin "P$A18") (pinfunction "DEC2_P$A18") (pintype "bidirectional"))
    )
    (net (code "45") (name "Net-(U1-DEC3V3)") (class "Default")
      (node (ref "C20") (pin "1") (pinfunction "1_1") (pintype "passive"))
      (node (ref "U1") (pin "P$AC5") (pinfunction "DEC3V3_P$AC5") (pintype "bidirectional"))
    )
    (net (code "46") (name "Net-(U1-DEC5)") (class "Default")
      (node (ref "C9") (pin "1") (pinfunction "1_1") (pintype "passive"))
      (node (ref "U1") (pin "P$N24") (pinfunction "DEC5_P$N24") (pintype "bidirectional"))
    )
    (net (code "47") (name "Net-(U1-XC1)") (class "Default")
      (node (ref "C1") (pin "1") (pinfunction "1_1") (pintype "passive"))
      (node (ref "U1") (pin "P$B24") (pinfunction "XC1_P$B24") (pintype "input"))
      (node (ref "X1") (pin "1") (pinfunction "1_1") (pintype "passive"))
    )
    (net (code "48") (name "Net-(U1-XC2)") (class "Default")
      (node (ref "C2") (pin "1") (pinfunction "1_1") (pintype "passive"))
      (node (ref "U1") (pin "P$A23") (pinfunction "XC2_P$A23") (pintype "output"))
      (node (ref "X1") (pin "3") (pinfunction "3_3") (pintype "passive"))
    )
    (net (code "49") (name "OUT+") (class "Default")
      (node (ref "IC2") (pin "A3") (pinfunction "OUT+_A3") (pintype "bidirectional"))
      (node (ref "TP_OP") (pin "TP") (pinfunction "TP_TP") (pintype "input"))
    )
    (net (code "50") (name "OUT-") (class "Default")
      (node (ref "IC2") (pin "C3") (pinfunction "OUT-_C3") (pintype "bidirectional"))
      (node (ref "TP_ON") (pin "TP") (pinfunction "TP_TP") (pintype "input"))
    )
    (net (code "51") (name "P0.00{slash}XL1") (class "Default")
      (node (ref "C17") (pin "2") (pinfunction "2_2") (pintype "passive"))
      (node (ref "U1") (pin "P$D2") (pinfunction "P0.00/XL1_P$D2") (pintype "bidirectional"))
      (node (ref "X2") (pin "1") (pinfunction "1_1") (pintype "passive"))
    )
    (net (code "52") (name "P0.01{slash}XL2") (class "Default")
      (node (ref "C18") (pin "2") (pinfunction "2_2") (pintype "passive"))
      (node (ref "U1") (pin "P$F2") (pinfunction "P0.01/XL2_P$F2") (pintype "bidirectional"))
      (node (ref "X2") (pin "2") (pinfunction "2_2") (pintype "passive"))
    )
    (net (code "53") (name "P0.04") (class "Default")
      (node (ref "U1") (pin "P$J1") (pinfunction "P0.04/AIN2_P$J1") (pintype "bidirectional"))
    )
    (net (code "54") (name "P0.09") (class "Default")
      (node (ref "U1") (pin "P$L24") (pinfunction "P0.09/NFC1_P$L24") (pintype "bidirectional"))
    )
    (net (code "55") (name "P0.13") (class "Default")
      (node (ref "U1") (pin "P$AD8") (pinfunction "P0.13_P$AD8") (pintype "bidirectional"))
    )
    (net (code "56") (name "P0.13{slash}1.5D") (class "Default")
      (node (ref "C30") (pin "2") (pinfunction "2_2") (pintype "passive"))
      (node (ref "R5") (pin "1") (pinfunction "1_1") (pintype "bidirectional"))
      (node (ref "SW_UP") (pin "2") (pinfunction "2_2") (pintype "passive"))
    )
    (net (code "57") (name "P0.14") (class "Default")
      (node (ref "U1") (pin "P$AC9") (pinfunction "P0.14_P$AC9") (pintype "bidirectional"))
    )
    (net (code "58") (name "P0.14{slash}1.5D") (class "Default")
      (node (ref "C31") (pin "2") (pinfunction "2_2") (pintype "passive"))
      (node (ref "R8") (pin "1") (pinfunction "1_1") (pintype "bidirectional"))
      (node (ref "SW_ENT") (pin "2") (pinfunction "2_2") (pintype "passive"))
    )
    (net (code "59") (name "P0.19") (class "Default")
      (node (ref "U1") (pin "P$AC15") (pinfunction "P0.19_P$AC15") (pintype "bidirectional"))
    )
    (net (code "60") (name "P0.20") (class "Default")
      (node (ref "U1") (pin "P$AD16") (pinfunction "P0.20_P$AD16") (pintype "bidirectional"))
    )
    (net (code "61") (name "P0.21") (class "Default")
      (node (ref "U1") (pin "P$AC17") (pinfunction "P0.21_P$AC17") (pintype "bidirectional"))
    )
    (net (code "62") (name "P0.22") (class "Default")
      (node (ref "U1") (pin "P$AD18") (pinfunction "P0.22_P$AD18") (pintype "bidirectional"))
    )
    (net (code "63") (name "P0.23") (class "Default")
      (node (ref "U1") (pin "P$AC19") (pinfunction "P0.23_P$AC19") (pintype "bidirectional"))
    )
    (net (code "64") (name "P0.24") (class "Default")
      (node (ref "U1") (pin "P$AD20") (pinfunction "P0.24_P$AD20") (pintype "bidirectional"))
    )
    (net (code "65") (name "P0.25") (class "Default")
      (node (ref "U1") (pin "P$AC21") (pinfunction "P0.25_P$AC21") (pintype "bidirectional"))
    )
    (net (code "66") (name "P0.26") (class "Default")
      (node (ref "U1") (pin "P$G1") (pinfunction "P0.26_P$G1") (pintype "bidirectional"))
    )
    (net (code "67") (name "P0.27") (class "Default")
      (node (ref "U1") (pin "P$H2") (pinfunction "P0.27_P$H2") (pintype "bidirectional"))
    )
    (net (code "68") (name "P0.28") (class "Default")
      (node (ref "U1") (pin "P$B11") (pinfunction "P0.28/AIN4_P$B11") (pintype "bidirectional"))
    )
    (net (code "69") (name "P0.29") (class "Default")
      (node (ref "U1") (pin "P$A10") (pinfunction "P0.29/AIN5_P$A10") (pintype "bidirectional"))
    )
    (net (code "70") (name "P0.30") (class "Default")
      (node (ref "U1") (pin "P$B9") (pinfunction "P0.30/AIN6_P$B9") (pintype "bidirectional"))
    )
    (net (code "71") (name "P0.31") (class "Default")
      (node (ref "U1") (pin "P$A8") (pinfunction "P0.31/AIN7_P$A8") (pintype "bidirectional"))
    )
    (net (code "72") (name "P1.01") (class "Default")
      (node (ref "U1") (pin "P$Y23") (pinfunction "P1.01_P$Y23") (pintype "bidirectional"))
    )
    (net (code "73") (name "P1.01{slash}1.6C") (class "Default")
      (node (ref "Q1") (pin "1") (pinfunction "G_1") (pintype "bidirectional"))
      (node (ref "R_PWR_EPD") (pin "1") (pinfunction "1_1") (pintype "bidirectional"))
    )
    (net (code "74") (name "P1.02") (class "Default")
      (node (ref "U1") (pin "P$W24") (pinfunction "P1.02_P$W24") (pintype "bidirectional"))
    )
    (net (code "75") (name "P1.02{slash}1.6C") (class "Default")
      (node (ref "C29") (pin "2") (pinfunction "2_2") (pintype "passive"))
      (node (ref "R7") (pin "1") (pinfunction "1_1") (pintype "bidirectional"))
      (node (ref "SW_DN") (pin "2") (pinfunction "2_2") (pintype "passive"))
    )
    (net (code "76") (name "P1.03") (class "Default")
      (node (ref "U1") (pin "P$V23") (pinfunction "P1.03_P$V23") (pintype "bidirectional"))
    )
    (net (code "77") (name "P1.04") (class "Default")
      (node (ref "U1") (pin "P$U24") (pinfunction "P1.04_P$U24") (pintype "bidirectional"))
    )
    (net (code "78") (name "P1.05") (class "Default")
      (node (ref "U1") (pin "P$T23") (pinfunction "P1.05_P$T23") (pintype "bidirectional"))
    )
    (net (code "79") (name "P1.06") (class "Default")
      (node (ref "U1") (pin "P$R24") (pinfunction "P1.06_P$R24") (pintype "bidirectional"))
    )
    (net (code "80") (name "P1.07") (class "Default")
      (node (ref "U1") (pin "P$P23") (pinfunction "P1.07_P$P23") (pintype "bidirectional"))
    )
    (net (code "81") (name "P1.09") (class "Default")
      (node (ref "U1") (pin "P$R1") (pinfunction "P1.09_P$R1") (pintype "bidirectional"))
    )
    (net (code "82") (name "P1.10") (class "Default")
      (node (ref "U1") (pin "P$A20") (pinfunction "P1.10_P$A20") (pintype "bidirectional"))
    )
    (net (code "83") (name "P1.11") (class "Default")
      (node (ref "U1") (pin "P$B19") (pinfunction "P1.11_P$B19") (pintype "bidirectional"))
    )
    (net (code "84") (name "P1.12") (class "Default")
      (node (ref "U1") (pin "P$B17") (pinfunction "P1.12_P$B17") (pintype "bidirectional"))
    )
    (net (code "85") (name "P1.13") (class "Default")
      (node (ref "U1") (pin "P$A16") (pinfunction "P1.13_P$A16") (pintype "bidirectional"))
    )
    (net (code "86") (name "P1.14") (class "Default")
      (node (ref "U1") (pin "P$B15") (pinfunction "P1.14_P$B15") (pintype "bidirectional"))
    )
    (net (code "87") (name "P1.15") (class "Default")
      (node (ref "U1") (pin "P$A14") (pinfunction "P1.15_P$A14") (pintype "bidirectional"))
    )
    (net (code "88") (name "PMIC_INT") (class "Default")
      (node (ref "IC1") (pin "A1") (pinfunction "~{INT}_A1") (pintype "bidirectional"))
      (node (ref "U1") (pin "P$T2") (pinfunction "P0.11_P$T2") (pintype "bidirectional"))
    )
    (net (code "89") (name "PREVGH") (class "Default")
      (node (ref "D5") (pin "1") (pinfunction "K_1") (pintype "bidirectional"))
      (node (ref "EPD_C9") (pin "2") (pinfunction "2_2") (pintype "passive"))
      (node (ref "J1") (pin "21") (pinfunction "21_21") (pintype "bidirectional"))
    )
    (net (code "90") (name "PREVGL") (class "Default")
      (node (ref "D2") (pin "2") (pinfunction "A_2") (pintype "bidirectional"))
      (node (ref "EPD_C11") (pin "2") (pinfunction "2_2") (pintype "passive"))
      (node (ref "J1") (pin "23") (pinfunction "23_23") (pintype "bidirectional"))
    )
    (net (code "91") (name "RESE") (class "Default")
      (node (ref "J1") (pin "3") (pinfunction "3_3") (pintype "bidirectional"))
      (node (ref "Q3") (pin "2") (pinfunction "S_2") (pintype "bidirectional"))
      (node (ref "R1_EP_ED") (pin "2") (pinfunction "2_2") (pintype "bidirectional"))
    )
    (net (code "92") (name "RESET") (class "Default")
      (node (ref "J2") (pin "6") (pinfunction "6_6") (pintype "bidirectional"))
      (node (ref "TP_RESET") (pin "TP") (pinfunction "TP_TP") (pintype "input"))
      (node (ref "U1") (pin "P$AC13") (pinfunction "P0.18/RESET_P$AC13") (pintype "bidirectional"))
    )
    (net (code "93") (name "RF") (class "Default")
      (node (ref "ANT1") (pin "1") (pinfunction "FEED_1") (pintype "input"))
      (node (ref "C22") (pin "1") (pinfunction "1_1") (pintype "passive"))
      (node (ref "C4") (pin "1") (pinfunction "1_1") (pintype "passive"))
      (node (ref "L1") (pin "2") (pinfunction "2_2") (pintype "passive"))
    )
    (net (code "94") (name "SCK") (class "Default")
      (node (ref "J1") (pin "13") (pinfunction "13_13") (pintype "bidirectional"))
      (node (ref "U1") (pin "P$A12") (pinfunction "P0.02/AIN0_P$A12") (pintype "bidirectional"))
    )
    (net (code "95") (name "SCL{slash}1.4C") (class "Default")
      (node (ref "IC2") (pin "C1") (pinfunction "SCL_C1") (pintype "bidirectional"))
      (node (ref "U3") (pin "7") (pinfunction "SCL_7") (pintype "input"))
    )
    (net (code "96") (name "SCL{slash}2.4C") (class "Default")
      (node (ref "IC1") (pin "B1") (pinfunction "SCL_B1") (pintype "bidirectional"))
      (node (ref "IC3") (pin "12") (pinfunction "SCX_12") (pintype "bidirectional"))
      (node (ref "R17") (pin "2") (pinfunction "2_2") (pintype "bidirectional"))
      (node (ref "R2") (pin "1") (pinfunction "1_1") (pintype "bidirectional"))
      (node (ref "R4") (pin "1") (pinfunction "1_1") (pintype "bidirectional"))
      (node (ref "TP_SCL") (pin "TP") (pinfunction "TP_TP") (pintype "input"))
      (node (ref "U1") (pin "P$M2") (pinfunction "P0.07_P$M2") (pintype "bidirectional"))
    )
    (net (code "97") (name "SDA{slash}1.4C") (class "Default")
      (node (ref "IC2") (pin "B2") (pinfunction "SDA_B2") (pintype "bidirectional"))
      (node (ref "U3") (pin "8") (pinfunction "SDA_8") (pintype "bidirectional"))
    )
    (net (code "98") (name "SDA{slash}2.4C") (class "Default")
      (node (ref "IC1") (pin "C1") (pinfunction "SDA_C1") (pintype "bidirectional"))
      (node (ref "IC3") (pin "2") (pinfunction "SDX_2") (pintype "bidirectional"))
      (node (ref "R18") (pin "2") (pinfunction "2_2") (pintype "bidirectional"))
      (node (ref "TP_SDA") (pin "TP") (pinfunction "TP_TP") (pintype "input"))
      (node (ref "U1") (pin "P$L1") (pinfunction "P0.06_P$L1") (pintype "bidirectional"))
    )
    (net (code "99") (name "SWDCLK") (class "Default")
      (node (ref "J2") (pin "4") (pinfunction "4_4") (pintype "bidirectional"))
      (node (ref "TP_SWDCLK") (pin "TP") (pinfunction "TP_TP") (pintype "input"))
      (node (ref "U1") (pin "P$AA24") (pinfunction "SWDCLK_P$AA24") (pintype "input"))
    )
    (net (code "100") (name "SWDIO") (class "Default")
      (node (ref "J2") (pin "2") (pinfunction "2_2") (pintype "bidirectional"))
      (node (ref "TP_SWDIO") (pin "TP") (pinfunction "TP_TP") (pintype "input"))
      (node (ref "U1") (pin "P$AC24") (pinfunction "SWDIO_P$AC24") (pintype "bidirectional"))
    )
    (net (code "101") (name "SWO") (class "Default")
      (node (ref "TP_SWO") (pin "TP") (pinfunction "TP_TP") (pintype "input"))
      (node (ref "U1") (pin "P$AD22") (pinfunction "P1.00_P$AD22") (pintype "bidirectional"))
    )
    (net (code "102") (name "VBAT") (class "Default")
      (node (ref "C27") (pin "2") (pinfunction "2_2") (pintype "passive"))
      (node (ref "C37") (pin "2") (pinfunction "2_2") (pintype "passive"))
      (node (ref "IC1") (pin "C2") (pinfunction "BAT_C2") (pintype "bidirectional"))
      (node (ref "TP_VBAT") (pin "TP") (pinfunction "TP_TP") (pintype "input"))
      (node (ref "U3") (pin "2") (pinfunction "CELL_2") (pintype "power_in"))
      (node (ref "U3") (pin "3") (pinfunction "VDD_3") (pintype "power_in"))
    )
    (net (code "103") (name "VBUS") (class "Default")
      (node (ref "C21") (pin "1") (pinfunction "1_1") (pintype "passive"))
      (node (ref "C38") (pin "2") (pinfunction "2_2") (pintype "passive"))
      (node (ref "C42") (pin "2") (pinfunction "2_2") (pintype "passive"))
      (node (ref "C43") (pin "1") (pinfunction "1_1") (pintype "passive"))
      (node (ref "D3") (pin "5") (pinfunction "VBUS_5") (pintype "bidirectional"))
      (node (ref "IC1") (pin "A2") (pinfunction "IN_A2") (pintype "bidirectional"))
      (node (ref "J4") (pin "A4_B9") (pinfunction "VBUS_A4_B9") (pintype "power_in"))
      (node (ref "J4") (pin "A9_B4") (pinfunction "VBUS_A9_B4") (pintype "power_in"))
      (node (ref "U1") (pin "P$AD2") (pinfunction "VBUS_P$AD2") (pintype "power_in"))
    )
    (net (code "104") (name "VREG") (class "Default")
      (node (ref "C23") (pin "2") (pinfunction "2_2") (pintype "passive"))
      (node (ref "C24") (pin "2") (pinfunction "2_2") (pintype "passive"))
      (node (ref "C39") (pin "1") (pinfunction "1_1") (pintype "passive"))
      (node (ref "IC1") (pin "B2") (pinfunction "SYS_B2") (pintype "bidirectional"))
      (node (ref "IC9") (pin "A1") (pinfunction "EN_A1") (pintype "bidirectional"))
      (node (ref "IC9") (pin "A2") (pinfunction "VIN_1_A2") (pintype "bidirectional"))
      (node (ref "IC9") (pin "A3") (pinfunction "VIN_2_A3") (pintype "bidirectional"))
      (node (ref "TP_VREG") (pin "TP") (pinfunction "TP_TP") (pintype "input"))
    )
    (net (code "105") (name "unconnected-(ANT1-NC-Pad2)") (class "Default")
      (node (ref "ANT1") (pin "2") (pinfunction "NC_2") (pintype "no_connect"))
    )
    (net (code "106") (name "unconnected-(IC3-ASCL-Pad11)") (class "Default")
      (node (ref "IC3") (pin "11") (pinfunction "ASCL_11") (pintype "bidirectional"))
    )
    (net (code "107") (name "unconnected-(IC3-ASDA-Pad4)") (class "Default")
      (node (ref "IC3") (pin "4") (pinfunction "ASDA_4") (pintype "bidirectional"))
    )
    (net (code "108") (name "unconnected-(J1-Pad1)") (class "Default")
      (node (ref "J1") (pin "1") (pinfunction "1_1") (pintype "bidirectional"))
    )
    (net (code "109") (name "unconnected-(J1-Pad6)") (class "Default")
      (node (ref "J1") (pin "6") (pinfunction "6_6") (pintype "bidirectional"))
    )
    (net (code "110") (name "unconnected-(J1-Pad7)") (class "Default")
      (node (ref "J1") (pin "7") (pinfunction "7_7") (pintype "bidirectional"))
    )
    (net (code "111") (name "unconnected-(J4-SBU1-PadA8)") (class "Default")
      (node (ref "J4") (pin "A8") (pinfunction "SBU1_A8") (pintype "bidirectional"))
    )
    (net (code "112") (name "unconnected-(J4-SBU2-PadB8)") (class "Default")
      (node (ref "J4") (pin "B8") (pinfunction "SBU2_B8") (pintype "bidirectional"))
    )
    (net (code "113") (name "unconnected-(U1-DCCH-PadP$AB2)") (class "Default")
      (node (ref "U1") (pin "P$AB2") (pinfunction "DCCH_P$AB2") (pintype "bidirectional"))
    )
  )
)
